# Kompass_MainframePTH.net
KiCad netlist of a schematic drawn in EAGLE
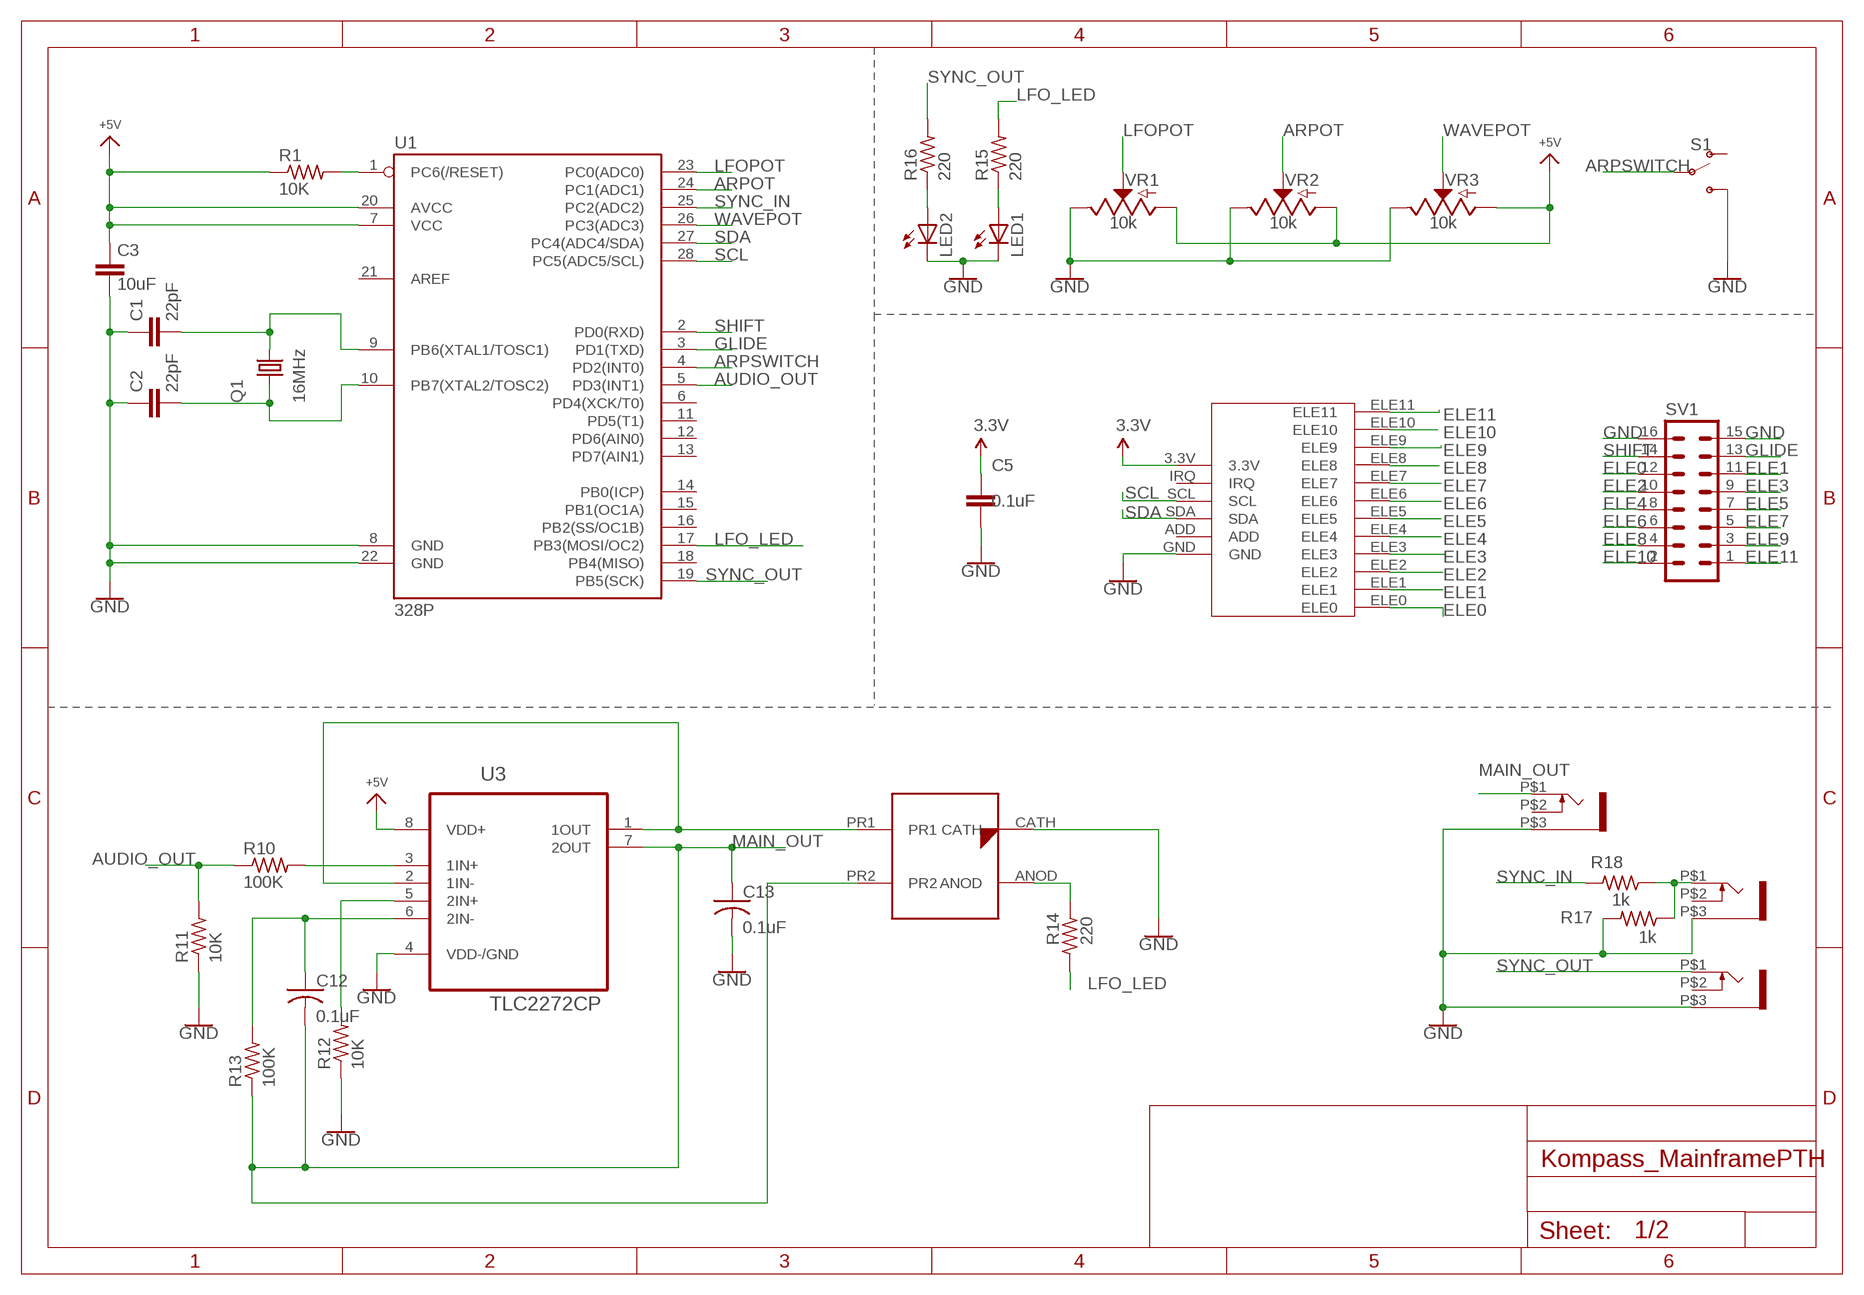
[diagram p0: schematic, sheet 1]
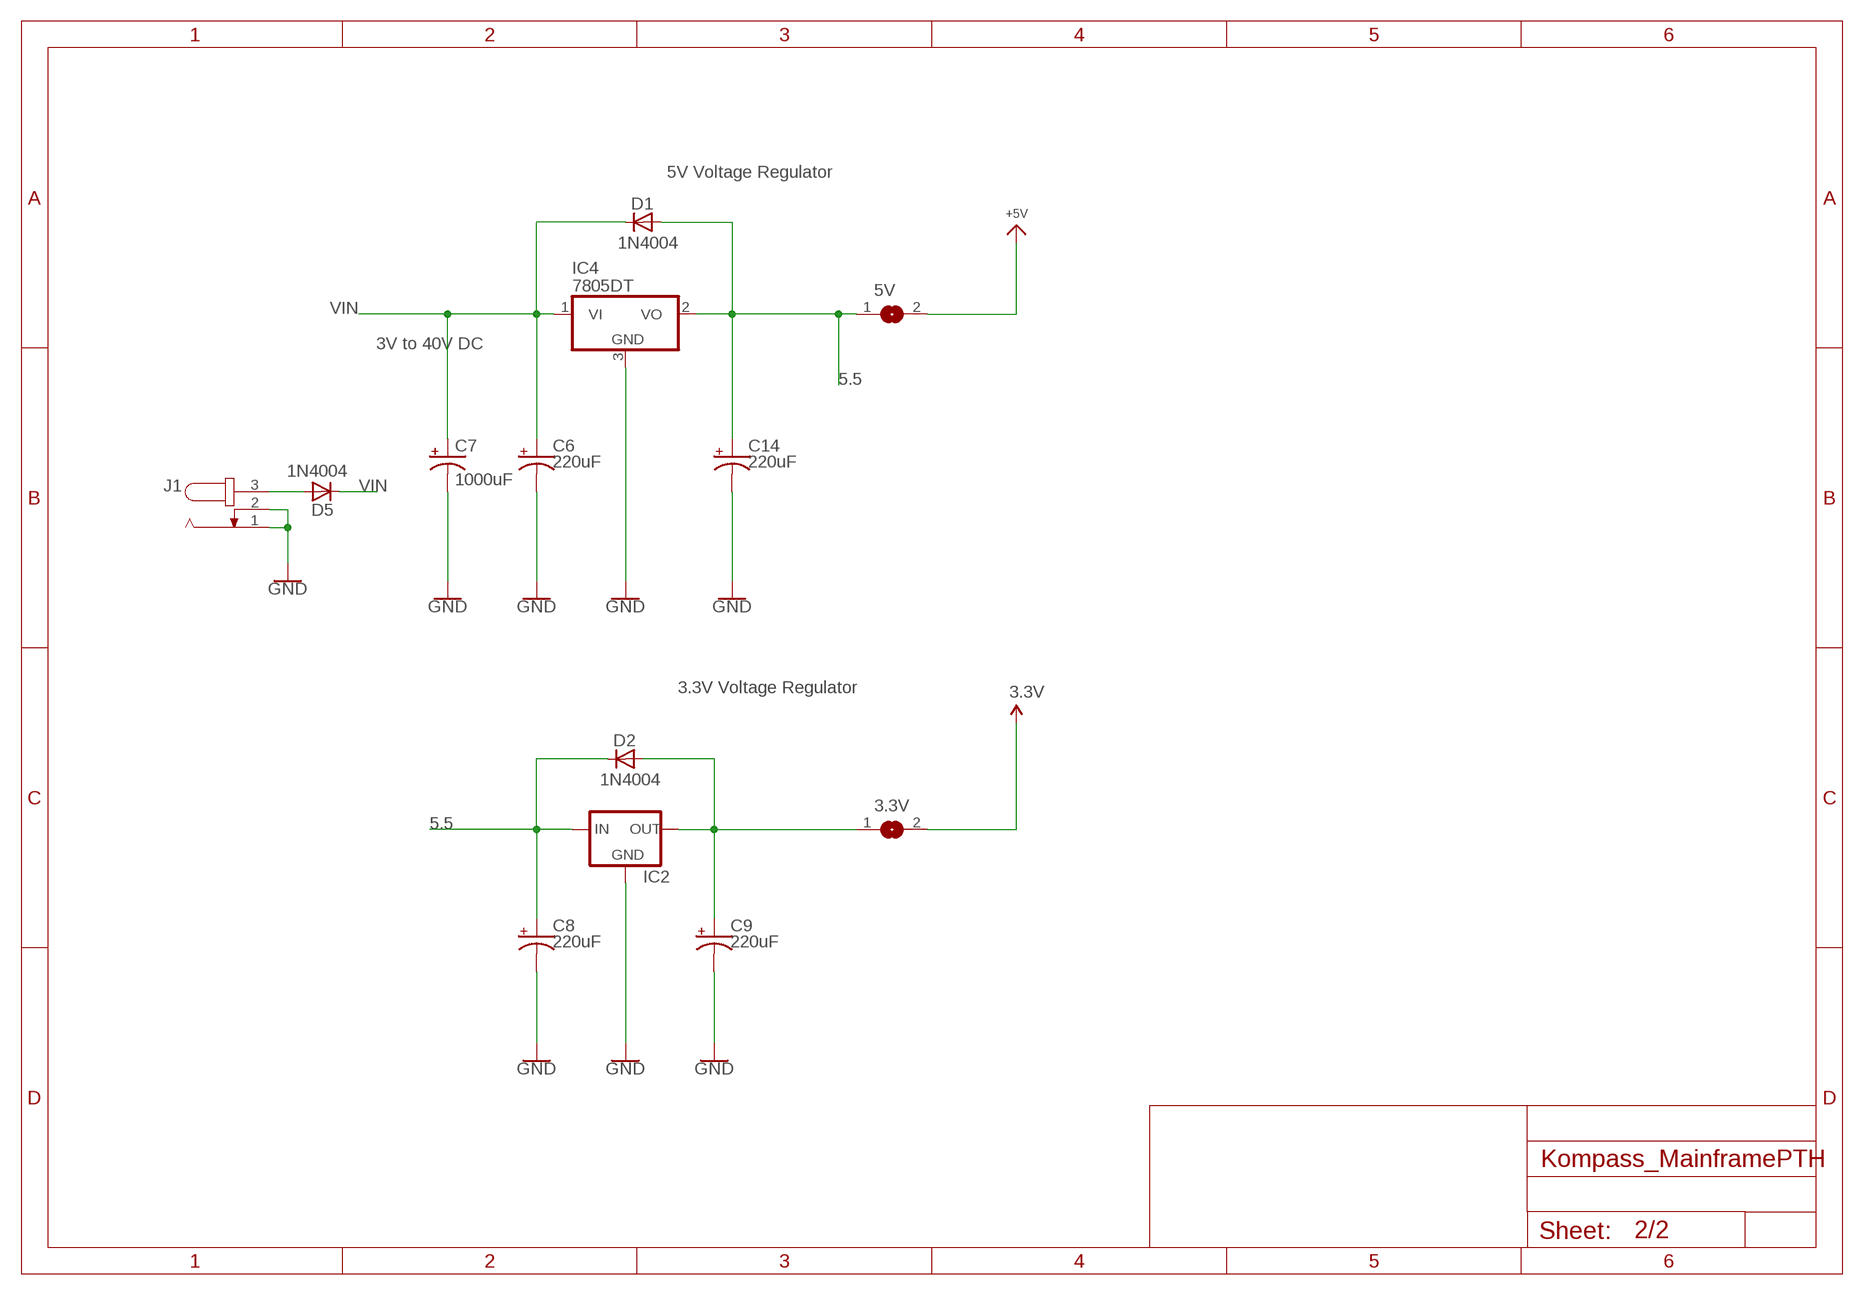
[diagram p1: schematic, sheet 2]

(export (version "E")
  (design (tool "Eeschema 10.0.6"))
  (components
    (comp (ref "C1")
      (value "22pF")
      (footprint "eagle-import:C2.5-3")
      (libsource (lib "eagle-import") (part "C2,5-3"))
    )
    (comp (ref "C2")
      (value "22pF")
      (footprint "eagle-import:C2.5-3")
      (libsource (lib "eagle-import") (part "C2,5-3"))
    )
    (comp (ref "C3")
      (value "10uF")
      (footprint "eagle-import:C025-025X050")
      (libsource (lib "eagle-import") (part "C-EU025-025X050"))
    )
    (comp (ref "C5")
      (value "0.1uF")
      (footprint "eagle-import:C2.5-3")
      (libsource (lib "eagle-import") (part "C2,5-3"))
    )
    (comp (ref "C12")
      (value "0.1uF")
      (footprint "eagle-import:C025-024X044")
      (libsource (lib "eagle-import") (part "C-US025-024X044"))
    )
    (comp (ref "C13")
      (value "0.1uF")
      (footprint "eagle-import:C025-024X044")
      (libsource (lib "eagle-import") (part "C-US025-024X044"))
    )
    (comp (ref "LED1")
      (value "LED3MM")
      (footprint "eagle-import:LED3MM")
      (libsource (lib "eagle-import") (part "LED3MM"))
    )
    (comp (ref "LED2")
      (value "LED3MM")
      (footprint "eagle-import:LED3MM")
      (libsource (lib "eagle-import") (part "LED3MM"))
    )
    (comp (ref "Q1")
      (value "16MHz")
      (footprint "eagle-import:HC49_S")
      (libsource (lib "eagle-import") (part "CRYSTALHC49S"))
    )
    (comp (ref "R1")
      (value "10K")
      (footprint "eagle-import:0204_5")
      (libsource (lib "eagle-import") (part "R-US_0204/5"))
    )
    (comp (ref "R10")
      (value "100K")
      (footprint "eagle-import:0204_5")
      (libsource (lib "eagle-import") (part "R-US_0204/5"))
    )
    (comp (ref "R11")
      (value "10K")
      (footprint "eagle-import:0204_5")
      (libsource (lib "eagle-import") (part "R-US_0204/5"))
    )
    (comp (ref "R12")
      (value "10K")
      (footprint "eagle-import:0204_5")
      (libsource (lib "eagle-import") (part "R-US_0204/5"))
    )
    (comp (ref "R13")
      (value "100K")
      (footprint "eagle-import:0204_5")
      (libsource (lib "eagle-import") (part "R-US_0204/5"))
    )
    (comp (ref "R14")
      (value "220")
      (footprint "eagle-import:0204_5")
      (libsource (lib "eagle-import") (part "R-US_0204/5"))
    )
    (comp (ref "R15")
      (value "220")
      (footprint "eagle-import:0204_5")
      (libsource (lib "eagle-import") (part "R-US_0204/5"))
    )
    (comp (ref "R16")
      (value "220")
      (footprint "eagle-import:0204_5")
      (libsource (lib "eagle-import") (part "R-US_0204/5"))
    )
    (comp (ref "R17")
      (value "1k")
      (footprint "eagle-import:0204_5")
      (libsource (lib "eagle-import") (part "R-US_0204/5"))
    )
    (comp (ref "R18")
      (value "1k")
      (footprint "eagle-import:0204_5")
      (libsource (lib "eagle-import") (part "R-US_0204/5"))
    )
    (comp (ref "S1")
      (value "SWITCH-SPDT-PTH-11.6X4.0MM")
      (footprint "eagle-import:SWITCH_SPDT_PTH_11.6X4.0MM")
      (libsource (lib "eagle-import") (part "SWITCH-SPDT-PTH-11.6X4.0MM"))
    )
    (comp (ref "SV1")
      (value "MA08-2")
      (footprint "eagle-import:MA08-2")
      (libsource (lib "eagle-import") (part "MA08-2"))
    )
    (comp (ref "U$1")
      (value "BOCUMA_VACTROLBMA_VACTROL_PTH")
      (footprint "eagle-import:BOCUMA_VACTROL")
      (libsource (lib "eagle-import") (part "BOCUMA_VACTROLBMA_VACTROL_PTH"))
    )
    (comp (ref "U$2")
      (value "WQP-PJ301M-12_JACK")
      (footprint "eagle-import:WQP-PJ301M-12_JACK")
      (libsource (lib "eagle-import") (part "WQP-PJ301M-12_JACK"))
    )
    (comp (ref "U$3")
      (value "WQP-PJ301M-12_JACK")
      (footprint "eagle-import:WQP-PJ301M-12_JACK")
      (libsource (lib "eagle-import") (part "WQP-PJ301M-12_JACK"))
    )
    (comp (ref "U$4")
      (value "WQP-PJ301M-12_JACK")
      (footprint "eagle-import:WQP-PJ301M-12_JACK")
      (libsource (lib "eagle-import") (part "WQP-PJ301M-12_JACK"))
    )
    (comp (ref "U$6")
      (value "MPR121_BREAKOUT")
      (footprint "eagle-import:MPR121_BREAKOUT")
      (libsource (lib "eagle-import") (part "MPR121_BREAKOUT"))
    )
    (comp (ref "U1")
      (value "328P")
      (footprint "eagle-import:DIP28")
      (libsource (lib "eagle-import") (part "ATMEGA328P_PDIP"))
    )
    (comp (ref "U3")
      (value "TLC2272CP")
      (footprint "eagle-import:DIP254P762X508-8")
      (fields (field (name "MF") "Texas Instruments"))
      (libsource (lib "eagle-import") (part "TLC2272CP"))
    )
    (comp (ref "VR1")
      (value "10k")
      (footprint "eagle-import:POT-PTH-ALPS")
      (libsource (lib "eagle-import") (part "POTENTIOMETER-PTH-9MM-1/20W-20%"))
    )
    (comp (ref "VR2")
      (value "10k")
      (footprint "eagle-import:POT-PTH-ALPS")
      (libsource (lib "eagle-import") (part "POTENTIOMETER-PTH-9MM-1/20W-20%"))
    )
    (comp (ref "VR3")
      (value "10k")
      (footprint "eagle-import:POT-PTH-ALPS")
      (libsource (lib "eagle-import") (part "POTENTIOMETER-PTH-9MM-1/20W-20%"))
    )
    (comp (ref "3.3V")
      (value "SJW")
      (footprint "eagle-import:SJW")
      (libsource (lib "eagle-import") (part "SJW"))
    )
    (comp (ref "5V")
      (value "SJW")
      (footprint "eagle-import:SJW")
      (libsource (lib "eagle-import") (part "SJW"))
    )
    (comp (ref "C6")
      (value "220uF")
      (footprint "eagle-import:E2,5-6E")
      (libsource (lib "eagle-import") (part "rcl_334_CPOL-USE2,5-6E"))
    )
    (comp (ref "C7")
      (value "1000uF")
      (footprint "eagle-import:E3,5-8")
      (libsource (lib "eagle-import") (part "CPOL-USE3.5-8"))
    )
    (comp (ref "C8")
      (value "220uF")
      (footprint "eagle-import:E2,5-6E")
      (libsource (lib "eagle-import") (part "rcl_334_CPOL-USE2,5-6E"))
    )
    (comp (ref "C9")
      (value "220uF")
      (footprint "eagle-import:E2,5-6E")
      (libsource (lib "eagle-import") (part "rcl_334_CPOL-USE2,5-6E"))
    )
    (comp (ref "C14")
      (value "220uF")
      (footprint "eagle-import:E2,5-6E")
      (libsource (lib "eagle-import") (part "rcl_334_CPOL-USE2,5-6E"))
    )
    (comp (ref "D1")
      (value "1N4004")
      (footprint "eagle-import:DO41-10")
      (libsource (lib "eagle-import") (part "1N4004"))
    )
    (comp (ref "D2")
      (value "1N4004")
      (footprint "eagle-import:DO41-10")
      (libsource (lib "eagle-import") (part "1N4004"))
    )
    (comp (ref "D5")
      (value "1N4004")
      (footprint "eagle-import:DO41-10")
      (libsource (lib "eagle-import") (part "1N4004"))
    )
    (comp (ref "IC2")
      (value "78LXX")
      (footprint "eagle-import:78LXX")
      (libsource (lib "eagle-import") (part "78LXX"))
    )
    (comp (ref "IC4")
      (value "7805DT")
      (footprint "eagle-import:TO252")
      (libsource (lib "eagle-import") (part "78DT05"))
    )
    (comp (ref "J1")
      (value "JACK-PLUG0")
      (footprint "eagle-import:SPC4077")
      (libsource (lib "eagle-import") (part "JACK-PLUG0"))
    )
  )
  (nets
    (net (code "1") (name "3.3V") (class "Default")
      (node (ref "3.3V") (pin "2") (pinfunction "2_2") (pintype "passive"))
      (node (ref "C5") (pin "1") (pinfunction "1_1") (pintype "passive"))
      (node (ref "U$6") (pin "3.3V") (pinfunction "3.3V_3.3V") (pintype "bidirectional"))
    )
    (net (code "2") (name "5.5") (class "Default")
      (node (ref "5V") (pin "1") (pinfunction "1_1") (pintype "passive"))
      (node (ref "C14") (pin "+") (pinfunction "+_+") (pintype "passive"))
      (node (ref "C8") (pin "+") (pinfunction "+_+") (pintype "passive"))
      (node (ref "D1") (pin "A") (pinfunction "A_A") (pintype "passive"))
      (node (ref "D2") (pin "C") (pinfunction "C_C") (pintype "passive"))
      (node (ref "IC2") (pin "IN") (pinfunction "IN_IN") (pintype "input"))
      (node (ref "IC4") (pin "2") (pinfunction "VO_2") (pintype "passive"))
    )
    (net (code "3") (name "ARPOT") (class "Default")
      (node (ref "U1") (pin "24") (pinfunction "PC1(ADC1)_24") (pintype "bidirectional"))
      (node (ref "VR2") (pin "P$2") (pinfunction "S_P$2") (pintype "passive"))
    )
    (net (code "4") (name "ARPSWITCH") (class "Default")
      (node (ref "S1") (pin "2") (pinfunction "P_2") (pintype "passive"))
      (node (ref "U1") (pin "4") (pinfunction "PD2(INT0)_4") (pintype "bidirectional"))
    )
    (net (code "5") (name "AUDIO_OUT") (class "Default")
      (node (ref "R10") (pin "1") (pinfunction "1_1") (pintype "passive"))
      (node (ref "R11") (pin "2") (pinfunction "2_2") (pintype "passive"))
      (node (ref "U1") (pin "5") (pinfunction "PD3(INT1)_5") (pintype "bidirectional"))
    )
    (net (code "6") (name "ELE0") (class "Default")
      (node (ref "SV1") (pin "12") (pinfunction "12_12") (pintype "passive"))
      (node (ref "U$6") (pin "ELE0") (pinfunction "ELE0_ELE0") (pintype "bidirectional"))
    )
    (net (code "7") (name "ELE1") (class "Default")
      (node (ref "SV1") (pin "11") (pinfunction "11_11") (pintype "passive"))
      (node (ref "U$6") (pin "ELE1") (pinfunction "ELE1_ELE1") (pintype "bidirectional"))
    )
    (net (code "8") (name "ELE2") (class "Default")
      (node (ref "SV1") (pin "10") (pinfunction "10_10") (pintype "passive"))
      (node (ref "U$6") (pin "ELE2") (pinfunction "ELE2_ELE2") (pintype "bidirectional"))
    )
    (net (code "9") (name "ELE3") (class "Default")
      (node (ref "SV1") (pin "9") (pinfunction "9_9") (pintype "passive"))
      (node (ref "U$6") (pin "ELE3") (pinfunction "ELE3_ELE3") (pintype "bidirectional"))
    )
    (net (code "10") (name "ELE4") (class "Default")
      (node (ref "SV1") (pin "8") (pinfunction "8_8") (pintype "passive"))
      (node (ref "U$6") (pin "ELE4") (pinfunction "ELE4_ELE4") (pintype "bidirectional"))
    )
    (net (code "11") (name "ELE5") (class "Default")
      (node (ref "SV1") (pin "7") (pinfunction "7_7") (pintype "passive"))
      (node (ref "U$6") (pin "ELE5") (pinfunction "ELE5_ELE5") (pintype "bidirectional"))
    )
    (net (code "12") (name "ELE6") (class "Default")
      (node (ref "SV1") (pin "6") (pinfunction "6_6") (pintype "passive"))
      (node (ref "U$6") (pin "ELE6") (pinfunction "ELE6_ELE6") (pintype "bidirectional"))
    )
    (net (code "13") (name "ELE7") (class "Default")
      (node (ref "SV1") (pin "5") (pinfunction "5_5") (pintype "passive"))
      (node (ref "U$6") (pin "ELE7") (pinfunction "ELE7_ELE7") (pintype "bidirectional"))
    )
    (net (code "14") (name "ELE8") (class "Default")
      (node (ref "SV1") (pin "4") (pinfunction "4_4") (pintype "passive"))
      (node (ref "U$6") (pin "ELE8") (pinfunction "ELE8_ELE8") (pintype "bidirectional"))
    )
    (net (code "15") (name "ELE9") (class "Default")
      (node (ref "SV1") (pin "3") (pinfunction "3_3") (pintype "passive"))
      (node (ref "U$6") (pin "ELE9") (pinfunction "ELE9_ELE9") (pintype "bidirectional"))
    )
    (net (code "16") (name "ELE10") (class "Default")
      (node (ref "SV1") (pin "2") (pinfunction "2_2") (pintype "passive"))
      (node (ref "U$6") (pin "ELE10") (pinfunction "ELE10_ELE10") (pintype "bidirectional"))
    )
    (net (code "17") (name "ELE11") (class "Default")
      (node (ref "SV1") (pin "1") (pinfunction "1_1") (pintype "passive"))
      (node (ref "U$6") (pin "ELE11") (pinfunction "ELE11_ELE11") (pintype "bidirectional"))
    )
    (net (code "18") (name "GLIDE") (class "Default")
      (node (ref "SV1") (pin "13") (pinfunction "13_13") (pintype "passive"))
      (node (ref "U1") (pin "3") (pinfunction "PD1(TXD)_3") (pintype "bidirectional"))
    )
    (net (code "19") (name "GND") (class "Default")
      (node (ref "C1") (pin "1") (pinfunction "1_1") (pintype "passive"))
      (node (ref "C13") (pin "2") (pinfunction "2_2") (pintype "passive"))
      (node (ref "C14") (pin "-") (pinfunction "-_-") (pintype "passive"))
      (node (ref "C2") (pin "1") (pinfunction "1_1") (pintype "passive"))
      (node (ref "C3") (pin "2") (pinfunction "2_2") (pintype "passive"))
      (node (ref "C5") (pin "2") (pinfunction "2_2") (pintype "passive"))
      (node (ref "C6") (pin "-") (pinfunction "-_-") (pintype "passive"))
      (node (ref "C7") (pin "-") (pinfunction "-_-") (pintype "passive"))
      (node (ref "C8") (pin "-") (pinfunction "-_-") (pintype "passive"))
      (node (ref "C9") (pin "-") (pinfunction "-_-") (pintype "passive"))
      (node (ref "IC2") (pin "GND") (pinfunction "GND_GND") (pintype "input"))
      (node (ref "IC4") (pin "3") (pinfunction "GND_3") (pintype "passive"))
      (node (ref "J1") (pin "1") (pinfunction "1_1") (pintype "passive"))
      (node (ref "J1") (pin "2") (pinfunction "2_2") (pintype "passive"))
      (node (ref "LED1") (pin "K") (pinfunction "C_K") (pintype "passive"))
      (node (ref "LED2") (pin "K") (pinfunction "C_K") (pintype "passive"))
      (node (ref "R11") (pin "1") (pinfunction "1_1") (pintype "passive"))
      (node (ref "R12") (pin "1") (pinfunction "1_1") (pintype "passive"))
      (node (ref "R17") (pin "2") (pinfunction "2_2") (pintype "passive"))
      (node (ref "S1") (pin "3") (pinfunction "S_3") (pintype "passive"))
      (node (ref "SV1") (pin "15") (pinfunction "15_15") (pintype "passive"))
      (node (ref "SV1") (pin "16") (pinfunction "16_16") (pintype "passive"))
      (node (ref "U$1") (pin "CATH") (pinfunction "CATH_CATH") (pintype "bidirectional"))
      (node (ref "U$2") (pin "P$3") (pinfunction "1_P$3") (pintype "passive"))
      (node (ref "U$3") (pin "P$3") (pinfunction "1_P$3") (pintype "passive"))
      (node (ref "U$4") (pin "P$3") (pinfunction "1_P$3") (pintype "passive"))
      (node (ref "U$6") (pin "GND") (pinfunction "GND_GND") (pintype "bidirectional"))
      (node (ref "U1") (pin "22") (pinfunction "GND_22") (pintype "bidirectional"))
      (node (ref "U1") (pin "8") (pinfunction "GND_8") (pintype "bidirectional"))
      (node (ref "U3") (pin "4") (pinfunction "VDD-/GND_4") (pintype "passive"))
      (node (ref "VR1") (pin "P$1") (pinfunction "E_P$1") (pintype "passive"))
      (node (ref "VR2") (pin "P$1") (pinfunction "E_P$1") (pintype "passive"))
      (node (ref "VR3") (pin "P$1") (pinfunction "E_P$1") (pintype "passive"))
    )
    (net (code "20") (name "LFOPOT") (class "Default")
      (node (ref "U1") (pin "23") (pinfunction "PC0(ADC0)_23") (pintype "bidirectional"))
      (node (ref "VR1") (pin "P$2") (pinfunction "S_P$2") (pintype "passive"))
    )
    (net (code "21") (name "LFO_LED") (class "Default")
      (node (ref "R14") (pin "1") (pinfunction "1_1") (pintype "passive"))
      (node (ref "R15") (pin "2") (pinfunction "2_2") (pintype "passive"))
      (node (ref "U1") (pin "17") (pinfunction "PB3(MOSI/OC2)_17") (pintype "bidirectional"))
    )
    (net (code "22") (name "MAIN_OUT") (class "Default")
      (node (ref "C12") (pin "2") (pinfunction "2_2") (pintype "passive"))
      (node (ref "C13") (pin "1") (pinfunction "1_1") (pintype "passive"))
      (node (ref "R13") (pin "1") (pinfunction "1_1") (pintype "passive"))
      (node (ref "U$1") (pin "PR2") (pinfunction "PR2_PR2") (pintype "bidirectional"))
      (node (ref "U$4") (pin "P$1") (pinfunction "2_P$1") (pintype "passive"))
      (node (ref "U3") (pin "7") (pinfunction "2OUT_7") (pintype "output"))
    )
    (net (code "23") (name "Net-(3.3V-Pad1)") (class "Default")
      (node (ref "3.3V") (pin "1") (pinfunction "1_1") (pintype "passive"))
      (node (ref "C9") (pin "+") (pinfunction "+_+") (pintype "passive"))
      (node (ref "D2") (pin "A") (pinfunction "A_A") (pintype "passive"))
      (node (ref "IC2") (pin "OUT") (pinfunction "OUT_OUT") (pintype "passive"))
    )
    (net (code "24") (name "Net-(D5-PadA)") (class "Default")
      (node (ref "D5") (pin "A") (pinfunction "A_A") (pintype "passive"))
      (node (ref "J1") (pin "3") (pinfunction "3_3") (pintype "passive"))
    )
    (net (code "25") (name "Net-(LED1-PadA)") (class "Default")
      (node (ref "LED1") (pin "A") (pinfunction "A_A") (pintype "passive"))
      (node (ref "R15") (pin "1") (pinfunction "1_1") (pintype "passive"))
    )
    (net (code "26") (name "Net-(LED2-PadA)") (class "Default")
      (node (ref "LED2") (pin "A") (pinfunction "A_A") (pintype "passive"))
      (node (ref "R16") (pin "1") (pinfunction "1_1") (pintype "passive"))
    )
    (net (code "27") (name "Net-(R14-Pad2)") (class "Default")
      (node (ref "R14") (pin "2") (pinfunction "2_2") (pintype "passive"))
      (node (ref "U$1") (pin "ANOD") (pinfunction "ANOD_ANOD") (pintype "bidirectional"))
    )
    (net (code "28") (name "Net-(U$2-2)") (class "Default")
      (node (ref "R17") (pin "1") (pinfunction "1_1") (pintype "passive"))
      (node (ref "R18") (pin "1") (pinfunction "1_1") (pintype "passive"))
      (node (ref "U$2") (pin "P$1") (pinfunction "2_P$1") (pintype "passive"))
    )
    (net (code "29") (name "Net-(U1-PB6(XTAL1{slash}TOSC1))") (class "Default")
      (node (ref "C1") (pin "2") (pinfunction "2_2") (pintype "passive"))
      (node (ref "Q1") (pin "2") (pinfunction "2_2") (pintype "passive"))
      (node (ref "U1") (pin "9") (pinfunction "PB6(XTAL1/TOSC1)_9") (pintype "bidirectional"))
    )
    (net (code "30") (name "Net-(U1-PB7(XTAL2{slash}TOSC2))") (class "Default")
      (node (ref "C2") (pin "2") (pinfunction "2_2") (pintype "passive"))
      (node (ref "Q1") (pin "1") (pinfunction "1_1") (pintype "passive"))
      (node (ref "U1") (pin "10") (pinfunction "PB7(XTAL2/TOSC2)_10") (pintype "bidirectional"))
    )
    (net (code "31") (name "Net-(U1-PC6({slash}RESET))") (class "Default")
      (node (ref "R1") (pin "2") (pinfunction "2_2") (pintype "passive"))
      (node (ref "U1") (pin "1") (pinfunction "PC6(/RESET)_1") (pintype "bidirectional"))
    )
    (net (code "32") (name "Net-(U3-1IN+)") (class "Default")
      (node (ref "R10") (pin "2") (pinfunction "2_2") (pintype "passive"))
      (node (ref "U3") (pin "3") (pinfunction "1IN+_3") (pintype "input"))
    )
    (net (code "33") (name "Net-(U3-1IN-)") (class "Default")
      (node (ref "U$1") (pin "PR1") (pinfunction "PR1_PR1") (pintype "bidirectional"))
      (node (ref "U3") (pin "1") (pinfunction "1OUT_1") (pintype "output"))
      (node (ref "U3") (pin "2") (pinfunction "1IN-_2") (pintype "input"))
    )
    (net (code "34") (name "Net-(U3-2IN+)") (class "Default")
      (node (ref "R12") (pin "2") (pinfunction "2_2") (pintype "passive"))
      (node (ref "U3") (pin "5") (pinfunction "2IN+_5") (pintype "input"))
    )
    (net (code "35") (name "Net-(U3-2IN-)") (class "Default")
      (node (ref "C12") (pin "1") (pinfunction "1_1") (pintype "passive"))
      (node (ref "R13") (pin "2") (pinfunction "2_2") (pintype "passive"))
      (node (ref "U3") (pin "6") (pinfunction "2IN-_6") (pintype "input"))
    )
    (net (code "36") (name "SCL") (class "Default")
      (node (ref "U$6") (pin "SCL") (pinfunction "SCL_SCL") (pintype "bidirectional"))
      (node (ref "U1") (pin "28") (pinfunction "PC5(ADC5/SCL)_28") (pintype "bidirectional"))
    )
    (net (code "37") (name "SDA") (class "Default")
      (node (ref "U$6") (pin "SDA") (pinfunction "SDA_SDA") (pintype "bidirectional"))
      (node (ref "U1") (pin "27") (pinfunction "PC4(ADC4/SDA)_27") (pintype "bidirectional"))
    )
    (net (code "38") (name "SHIFT") (class "Default")
      (node (ref "SV1") (pin "14") (pinfunction "14_14") (pintype "passive"))
      (node (ref "U1") (pin "2") (pinfunction "PD0(RXD)_2") (pintype "bidirectional"))
    )
    (net (code "39") (name "SYNC_IN") (class "Default")
      (node (ref "R18") (pin "2") (pinfunction "2_2") (pintype "passive"))
      (node (ref "U1") (pin "25") (pinfunction "PC2(ADC2)_25") (pintype "bidirectional"))
    )
    (net (code "40") (name "SYNC_OUT") (class "Default")
      (node (ref "R16") (pin "2") (pinfunction "2_2") (pintype "passive"))
      (node (ref "U$3") (pin "P$1") (pinfunction "2_P$1") (pintype "passive"))
      (node (ref "U1") (pin "19") (pinfunction "PB5(SCK)_19") (pintype "bidirectional"))
    )
    (net (code "41") (name "VCC") (class "Default")
      (node (ref "5V") (pin "2") (pinfunction "2_2") (pintype "passive"))
      (node (ref "C3") (pin "1") (pinfunction "1_1") (pintype "passive"))
      (node (ref "R1") (pin "1") (pinfunction "1_1") (pintype "passive"))
      (node (ref "U1") (pin "20") (pinfunction "AVCC_20") (pintype "bidirectional"))
      (node (ref "U1") (pin "7") (pinfunction "VCC_7") (pintype "bidirectional"))
      (node (ref "U3") (pin "8") (pinfunction "VDD+_8") (pintype "power_in"))
      (node (ref "VR1") (pin "P$3") (pinfunction "A_P$3") (pintype "passive"))
      (node (ref "VR2") (pin "P$3") (pinfunction "A_P$3") (pintype "passive"))
      (node (ref "VR3") (pin "P$3") (pinfunction "A_P$3") (pintype "passive"))
    )
    (net (code "42") (name "VIN") (class "Default")
      (node (ref "C6") (pin "+") (pinfunction "+_+") (pintype "passive"))
      (node (ref "C7") (pin "+") (pinfunction "+_+") (pintype "passive"))
      (node (ref "D1") (pin "C") (pinfunction "C_C") (pintype "passive"))
      (node (ref "D5") (pin "C") (pinfunction "C_C") (pintype "passive"))
      (node (ref "IC4") (pin "1") (pinfunction "VI_1") (pintype "input"))
    )
    (net (code "43") (name "WAVEPOT") (class "Default")
      (node (ref "U1") (pin "26") (pinfunction "PC3(ADC3)_26") (pintype "bidirectional"))
      (node (ref "VR3") (pin "P$2") (pinfunction "S_P$2") (pintype "passive"))
    )
    (net (code "44") (name "unconnected-(S1-O-Pad1)") (class "Default")
      (node (ref "S1") (pin "1") (pinfunction "O_1") (pintype "passive"))
    )
    (net (code "45") (name "unconnected-(U$2-3-PadP$2)") (class "Default")
      (node (ref "U$2") (pin "P$2") (pinfunction "3_P$2") (pintype "passive"))
    )
    (net (code "46") (name "unconnected-(U$3-3-PadP$2)") (class "Default")
      (node (ref "U$3") (pin "P$2") (pinfunction "3_P$2") (pintype "passive"))
    )
    (net (code "47") (name "unconnected-(U$4-3-PadP$2)") (class "Default")
      (node (ref "U$4") (pin "P$2") (pinfunction "3_P$2") (pintype "passive"))
    )
    (net (code "48") (name "unconnected-(U$6-PadADD)") (class "Default")
      (node (ref "U$6") (pin "ADD") (pinfunction "ADD_ADD") (pintype "bidirectional"))
    )
    (net (code "49") (name "unconnected-(U$6-PadIRQ)") (class "Default")
      (node (ref "U$6") (pin "IRQ") (pinfunction "IRQ_IRQ") (pintype "bidirectional"))
    )
    (net (code "50") (name "unconnected-(U1-AREF-Pad21)") (class "Default")
      (node (ref "U1") (pin "21") (pinfunction "AREF_21") (pintype "bidirectional"))
    )
    (net (code "51") (name "unconnected-(U1-PB0(ICP)-Pad14)") (class "Default")
      (node (ref "U1") (pin "14") (pinfunction "PB0(ICP)_14") (pintype "bidirectional"))
    )
    (net (code "52") (name "unconnected-(U1-PB1(OC1A)-Pad15)") (class "Default")
      (node (ref "U1") (pin "15") (pinfunction "PB1(OC1A)_15") (pintype "bidirectional"))
    )
    (net (code "53") (name "unconnected-(U1-PB2(SS{slash}OC1B)-Pad16)") (class "Default")
      (node (ref "U1") (pin "16") (pinfunction "PB2(SS/OC1B)_16") (pintype "bidirectional"))
    )
    (net (code "54") (name "unconnected-(U1-PB4(MISO)-Pad18)") (class "Default")
      (node (ref "U1") (pin "18") (pinfunction "PB4(MISO)_18") (pintype "bidirectional"))
    )
    (net (code "55") (name "unconnected-(U1-PD4(XCK{slash}T0)-Pad6)") (class "Default")
      (node (ref "U1") (pin "6") (pinfunction "PD4(XCK/T0)_6") (pintype "bidirectional"))
    )
    (net (code "56") (name "unconnected-(U1-PD5(T1)-Pad11)") (class "Default")
      (node (ref "U1") (pin "11") (pinfunction "PD5(T1)_11") (pintype "bidirectional"))
    )
    (net (code "57") (name "unconnected-(U1-PD6(AIN0)-Pad12)") (class "Default")
      (node (ref "U1") (pin "12") (pinfunction "PD6(AIN0)_12") (pintype "bidirectional"))
    )
    (net (code "58") (name "unconnected-(U1-PD7(AIN1)-Pad13)") (class "Default")
      (node (ref "U1") (pin "13") (pinfunction "PD7(AIN1)_13") (pintype "bidirectional"))
    )
  )
)
